# Block_HDMI_DP_DSI_USBSS_and_PCIe.net
KiCad netlist of a schematic drawn in Altium Designer
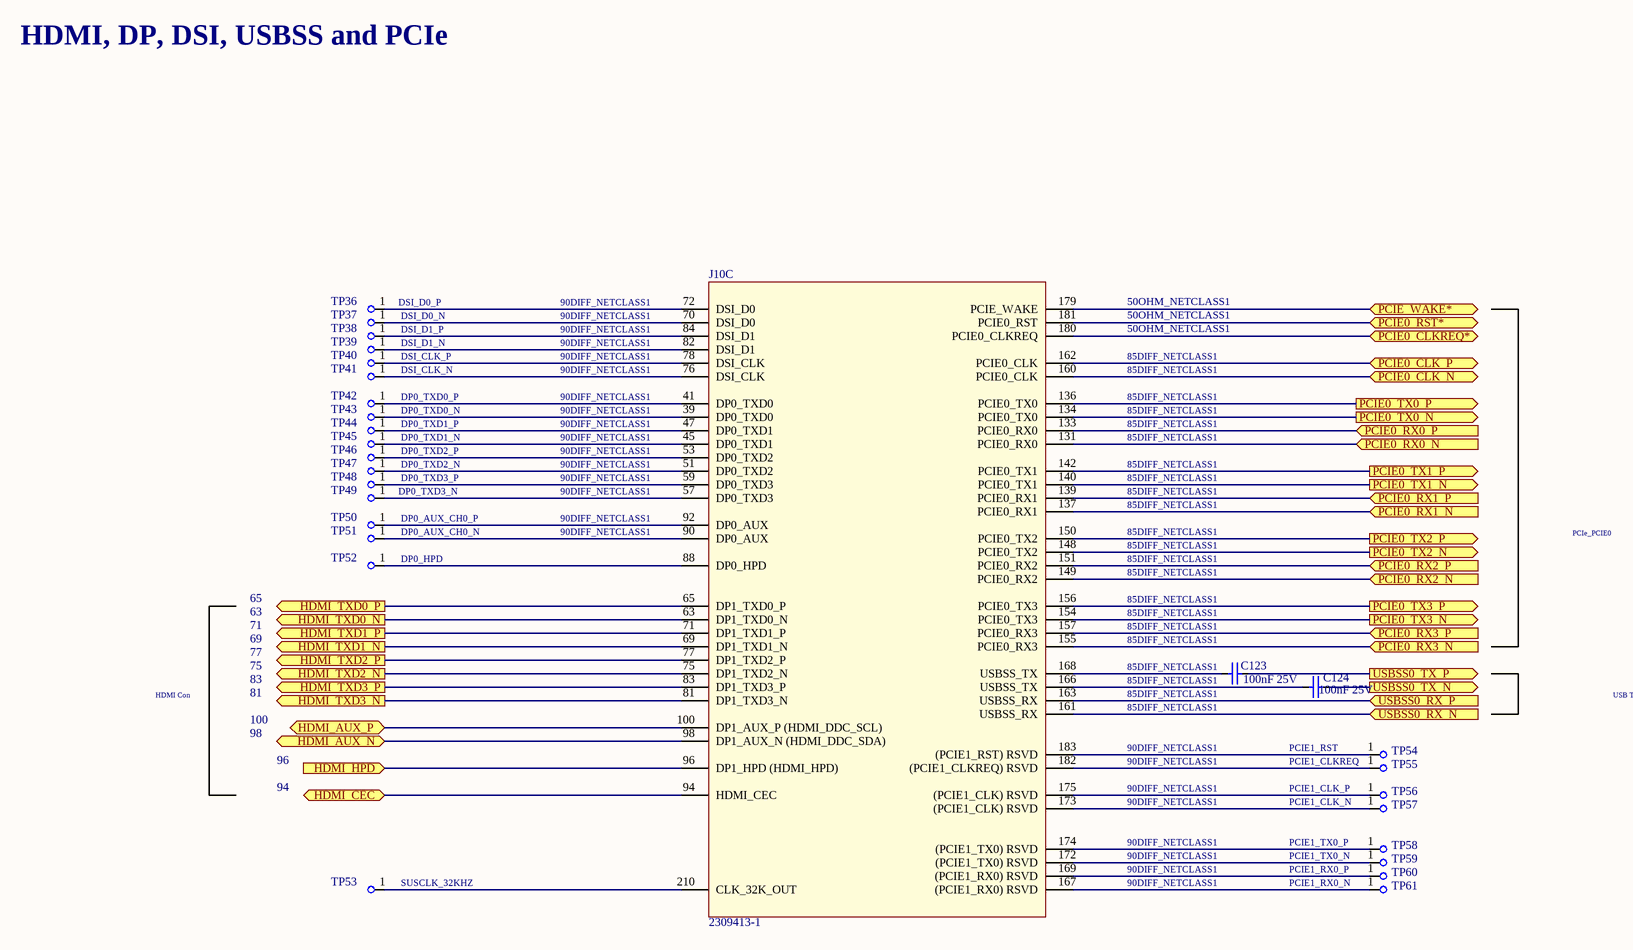
[diagram p0: Block_HDMI, DP, DSI, USBSS and PCIe.SchDoc]

(export (version "E")
  (design (tool "Eeschema 10.0.6"))
  (components
    (comp (ref "C123")
      (value "100nF 25V")
      (footprint "C0402")
      (description "CAP CER 0.1UF 25V X5R 0402 / High Value Multilayer Ceramic Capacitors (High dielectric type)")
      (fields
        (field (name "MANUFACTURER") "Taiyo Yuden")
        (field (name "MANUFACTURER PART NUMBER") "TMK105BJ104KV-F")
      )
      (libsource (lib "GM_Altium_Library") (part "TMK105BJ104KV-F"))
    )
    (comp (ref "C124")
      (value "100nF 25V")
      (footprint "C0402")
      (description "CAP CER 0.1UF 25V X5R 0402 / High Value Multilayer Ceramic Capacitors (High dielectric type)")
      (fields
        (field (name "MANUFACTURER") "Taiyo Yuden")
        (field (name "MANUFACTURER PART NUMBER") "TMK105BJ104KV-F")
      )
      (libsource (lib "GM_Altium_Library") (part "TMK105BJ104KV-F"))
    )
    (comp (ref "J10")
      (value "2309413-1")
      (footprint "2309413-1")
      (description "Conn DDR4 DIMM Socket SKT 260 POS 0.5mm Solder RA SMD T/R")
      (fields (field (name "MANUFACTURER") "TE Connectivity"))
      (libsource (lib "GM_Altium_Library") (part "2309413-1"))
    )
    (comp (ref "TP36")
      (value "DSI_D0_P")
      (footprint "TestPoint_Pad_D1.0mm")
      (libsource (lib "GM_Altium_Library") (part "TestPoint_D1mm"))
    )
    (comp (ref "TP37")
      (value "DSI_D0_N")
      (footprint "TestPoint_Pad_D1.0mm")
      (libsource (lib "GM_Altium_Library") (part "TestPoint_D1mm"))
    )
    (comp (ref "TP38")
      (value "DSI_D1_P")
      (footprint "TestPoint_Pad_D1.0mm")
      (libsource (lib "GM_Altium_Library") (part "TestPoint_D1mm"))
    )
    (comp (ref "TP39")
      (value "DSI_D1_N")
      (footprint "TestPoint_Pad_D1.0mm")
      (libsource (lib "GM_Altium_Library") (part "TestPoint_D1mm"))
    )
    (comp (ref "TP40")
      (value "DSI_CLK_P")
      (footprint "TestPoint_Pad_D1.0mm")
      (libsource (lib "GM_Altium_Library") (part "TestPoint_D1mm"))
    )
    (comp (ref "TP41")
      (value "DSI_CLK_N")
      (footprint "TestPoint_Pad_D1.0mm")
      (libsource (lib "GM_Altium_Library") (part "TestPoint_D1mm"))
    )
    (comp (ref "TP42")
      (value "DP0_TXD0_P")
      (footprint "TestPoint_Pad_D1.0mm")
      (libsource (lib "GM_Altium_Library") (part "TestPoint_D1mm"))
    )
    (comp (ref "TP43")
      (value "DP0_TXD0_N")
      (footprint "TestPoint_Pad_D1.0mm")
      (libsource (lib "GM_Altium_Library") (part "TestPoint_D1mm"))
    )
    (comp (ref "TP44")
      (value "DP0_TXD1_P")
      (footprint "TestPoint_Pad_D1.0mm")
      (libsource (lib "GM_Altium_Library") (part "TestPoint_D1mm"))
    )
    (comp (ref "TP45")
      (value "DP0_TXD1_N")
      (footprint "TestPoint_Pad_D1.0mm")
      (libsource (lib "GM_Altium_Library") (part "TestPoint_D1mm"))
    )
    (comp (ref "TP46")
      (value "DP0_TXD2_P")
      (footprint "TestPoint_Pad_D1.0mm")
      (libsource (lib "GM_Altium_Library") (part "TestPoint_D1mm"))
    )
    (comp (ref "TP47")
      (value "DP0_TXD2_N")
      (footprint "TestPoint_Pad_D1.0mm")
      (libsource (lib "GM_Altium_Library") (part "TestPoint_D1mm"))
    )
    (comp (ref "TP48")
      (value "DP0_TXD3_P")
      (footprint "TestPoint_Pad_D1.0mm")
      (libsource (lib "GM_Altium_Library") (part "TestPoint_D1mm"))
    )
    (comp (ref "TP49")
      (value "DP0_TXD3_N")
      (footprint "TestPoint_Pad_D1.0mm")
      (libsource (lib "GM_Altium_Library") (part "TestPoint_D1mm"))
    )
    (comp (ref "TP50")
      (value "DP0_AUX_CH0_P")
      (footprint "TestPoint_Pad_D1.0mm")
      (libsource (lib "GM_Altium_Library") (part "TestPoint_D1mm"))
    )
    (comp (ref "TP51")
      (value "DP0_AUX_CH0_N")
      (footprint "TestPoint_Pad_D1.0mm")
      (libsource (lib "GM_Altium_Library") (part "TestPoint_D1mm"))
    )
    (comp (ref "TP52")
      (value "DP0_HPD")
      (footprint "TestPoint_Pad_D1.0mm")
      (libsource (lib "GM_Altium_Library") (part "TestPoint_D1mm"))
    )
    (comp (ref "TP53")
      (value "SUSCLK_32KHZ")
      (footprint "TestPoint_Pad_D1.0mm")
      (libsource (lib "GM_Altium_Library") (part "TestPoint_D1mm"))
    )
    (comp (ref "TP54")
      (value "PCIE1_RST")
      (footprint "TestPoint_Pad_D1.0mm")
      (libsource (lib "GM_Altium_Library") (part "TestPoint_D1mm"))
    )
    (comp (ref "TP55")
      (value "PCIE1_CLKREQ")
      (footprint "TestPoint_Pad_D1.0mm")
      (libsource (lib "GM_Altium_Library") (part "TestPoint_D1mm"))
    )
    (comp (ref "TP56")
      (value "PCIE1_CLK_P")
      (footprint "TestPoint_Pad_D1.0mm")
      (libsource (lib "GM_Altium_Library") (part "TestPoint_D1mm"))
    )
    (comp (ref "TP57")
      (value "PCIE1_CLK_N")
      (footprint "TestPoint_Pad_D1.0mm")
      (libsource (lib "GM_Altium_Library") (part "TestPoint_D1mm"))
    )
    (comp (ref "TP58")
      (value "PCIE1_TX0_P")
      (footprint "TestPoint_Pad_D1.0mm")
      (libsource (lib "GM_Altium_Library") (part "TestPoint_D1mm"))
    )
    (comp (ref "TP59")
      (value "PCIE1_TX0_N")
      (footprint "TestPoint_Pad_D1.0mm")
      (libsource (lib "GM_Altium_Library") (part "TestPoint_D1mm"))
    )
    (comp (ref "TP60")
      (value "PCIE1_RX0_P")
      (footprint "TestPoint_Pad_D1.0mm")
      (libsource (lib "GM_Altium_Library") (part "TestPoint_D1mm"))
    )
    (comp (ref "TP61")
      (value "PCIE1_RX0_N")
      (footprint "TestPoint_Pad_D1.0mm")
      (libsource (lib "GM_Altium_Library") (part "TestPoint_D1mm"))
    )
  )
  (nets
    (net (code "1") (name "/HDMI_AUX_N") (class "Default")
      (node (ref "J10") (pin "98") (pinfunction "DP1_AUX_N_(HDMI_DDC_SDA)_98") (pintype "passive"))
    )
    (net (code "2") (name "/HDMI_AUX_P") (class "Default")
      (node (ref "J10") (pin "100") (pinfunction "DP1_AUX_P_(HDMI_DDC_SCL)_100") (pintype "passive"))
    )
    (net (code "3") (name "/HDMI_CEC") (class "Default")
      (node (ref "J10") (pin "94") (pinfunction "HDMI_CEC_94") (pintype "passive"))
    )
    (net (code "4") (name "/HDMI_HPD") (class "Default")
      (node (ref "J10") (pin "96") (pinfunction "DP1_HPD_(HDMI_HPD)_96") (pintype "passive"))
    )
    (net (code "5") (name "/HDMI_TXD0_N") (class "Default")
      (node (ref "J10") (pin "63") (pinfunction "DP1_TXD0_N_63") (pintype "passive"))
    )
    (net (code "6") (name "/HDMI_TXD0_P") (class "Default")
      (node (ref "J10") (pin "65") (pinfunction "DP1_TXD0_P_65") (pintype "passive"))
    )
    (net (code "7") (name "/HDMI_TXD1_N") (class "Default")
      (node (ref "J10") (pin "69") (pinfunction "DP1_TXD1_N_69") (pintype "passive"))
    )
    (net (code "8") (name "/HDMI_TXD1_P") (class "Default")
      (node (ref "J10") (pin "71") (pinfunction "DP1_TXD1_P_71") (pintype "passive"))
    )
    (net (code "9") (name "/HDMI_TXD2_N") (class "Default")
      (node (ref "J10") (pin "75") (pinfunction "DP1_TXD2_N_75") (pintype "passive"))
    )
    (net (code "10") (name "/HDMI_TXD2_P") (class "Default")
      (node (ref "J10") (pin "77") (pinfunction "DP1_TXD2_P_77") (pintype "passive"))
    )
    (net (code "11") (name "/HDMI_TXD3_N") (class "Default")
      (node (ref "J10") (pin "81") (pinfunction "DP1_TXD3_N_81") (pintype "passive"))
    )
    (net (code "12") (name "/HDMI_TXD3_P") (class "Default")
      (node (ref "J10") (pin "83") (pinfunction "DP1_TXD3_P_83") (pintype "passive"))
    )
    (net (code "13") (name "/PCIE0_CLKREQ*") (class "Default")
      (node (ref "J10") (pin "180") (pinfunction "PCIE0_CLKREQ_180") (pintype "passive"))
    )
    (net (code "14") (name "/PCIE0_CLK_N") (class "Default")
      (node (ref "J10") (pin "160") (pinfunction "PCIE0_CLK_160") (pintype "passive"))
    )
    (net (code "15") (name "/PCIE0_CLK_P") (class "Default")
      (node (ref "J10") (pin "162") (pinfunction "PCIE0_CLK_162") (pintype "passive"))
    )
    (net (code "16") (name "/PCIE0_RST*") (class "Default")
      (node (ref "J10") (pin "181") (pinfunction "PCIE0_RST_181") (pintype "passive"))
    )
    (net (code "17") (name "/PCIE0_RX0_N") (class "Default")
      (node (ref "J10") (pin "131") (pinfunction "PCIE0_RX0_131") (pintype "passive"))
    )
    (net (code "18") (name "/PCIE0_RX0_P") (class "Default")
      (node (ref "J10") (pin "133") (pinfunction "PCIE0_RX0_133") (pintype "passive"))
    )
    (net (code "19") (name "/PCIE0_RX1_N") (class "Default")
      (node (ref "J10") (pin "137") (pinfunction "PCIE0_RX1_137") (pintype "passive"))
    )
    (net (code "20") (name "/PCIE0_RX1_P") (class "Default")
      (node (ref "J10") (pin "139") (pinfunction "PCIE0_RX1_139") (pintype "passive"))
    )
    (net (code "21") (name "/PCIE0_RX2_N") (class "Default")
      (node (ref "J10") (pin "149") (pinfunction "PCIE0_RX2_149") (pintype "passive"))
    )
    (net (code "22") (name "/PCIE0_RX2_P") (class "Default")
      (node (ref "J10") (pin "151") (pinfunction "PCIE0_RX2_151") (pintype "passive"))
    )
    (net (code "23") (name "/PCIE0_RX3_N") (class "Default")
      (node (ref "J10") (pin "155") (pinfunction "PCIE0_RX3_155") (pintype "passive"))
    )
    (net (code "24") (name "/PCIE0_RX3_P") (class "Default")
      (node (ref "J10") (pin "157") (pinfunction "PCIE0_RX3_157") (pintype "passive"))
    )
    (net (code "25") (name "/PCIE0_TX0_N") (class "Default")
      (node (ref "J10") (pin "134") (pinfunction "PCIE0_TX0_134") (pintype "passive"))
    )
    (net (code "26") (name "/PCIE0_TX0_P") (class "Default")
      (node (ref "J10") (pin "136") (pinfunction "PCIE0_TX0_136") (pintype "passive"))
    )
    (net (code "27") (name "/PCIE0_TX1_N") (class "Default")
      (node (ref "J10") (pin "140") (pinfunction "PCIE0_TX1_140") (pintype "passive"))
    )
    (net (code "28") (name "/PCIE0_TX1_P") (class "Default")
      (node (ref "J10") (pin "142") (pinfunction "PCIE0_TX1_142") (pintype "passive"))
    )
    (net (code "29") (name "/PCIE0_TX2_N") (class "Default")
      (node (ref "J10") (pin "148") (pinfunction "PCIE0_TX2_148") (pintype "passive"))
    )
    (net (code "30") (name "/PCIE0_TX2_P") (class "Default")
      (node (ref "J10") (pin "150") (pinfunction "PCIE0_TX2_150") (pintype "passive"))
    )
    (net (code "31") (name "/PCIE0_TX3_N") (class "Default")
      (node (ref "J10") (pin "154") (pinfunction "PCIE0_TX3_154") (pintype "passive"))
    )
    (net (code "32") (name "/PCIE0_TX3_P") (class "Default")
      (node (ref "J10") (pin "156") (pinfunction "PCIE0_TX3_156") (pintype "passive"))
    )
    (net (code "33") (name "/PCIE_WAKE*") (class "Default")
      (node (ref "J10") (pin "179") (pinfunction "PCIE_WAKE_179") (pintype "passive"))
    )
    (net (code "34") (name "/USBSS0_RX_N") (class "Default")
      (node (ref "J10") (pin "161") (pinfunction "USBSS_RX_161") (pintype "passive"))
    )
    (net (code "35") (name "/USBSS0_RX_P") (class "Default")
      (node (ref "J10") (pin "163") (pinfunction "USBSS_RX_163") (pintype "passive"))
    )
    (net (code "36") (name "/USBSS0_TX_N") (class "Default")
      (node (ref "C124") (pin "2") (pinfunction "2_2") (pintype "passive"))
    )
    (net (code "37") (name "/USBSS0_TX_P") (class "Default")
      (node (ref "C123") (pin "2") (pinfunction "2_2") (pintype "passive"))
    )
    (net (code "38") (name "Net-(C123-Pad1)") (class "Default")
      (node (ref "C123") (pin "1") (pinfunction "1_1") (pintype "passive"))
      (node (ref "J10") (pin "168") (pinfunction "USBSS_TX_168") (pintype "passive"))
    )
    (net (code "39") (name "Net-(C124-Pad1)") (class "Default")
      (node (ref "C124") (pin "1") (pinfunction "1_1") (pintype "passive"))
      (node (ref "J10") (pin "166") (pinfunction "USBSS_TX_166") (pintype "passive"))
    )
    (net (code "40") (name "Net-(J10C-(PCIE1_CLK)_RSVD-Pad173)") (class "Default")
      (node (ref "J10") (pin "173") (pinfunction "(PCIE1_CLK)_RSVD_173") (pintype "passive"))
      (node (ref "TP57") (pin "1") (pinfunction "1_1") (pintype "passive"))
    )
    (net (code "41") (name "Net-(J10C-(PCIE1_CLK)_RSVD-Pad175)") (class "Default")
      (node (ref "J10") (pin "175") (pinfunction "(PCIE1_CLK)_RSVD_175") (pintype "passive"))
      (node (ref "TP56") (pin "1") (pinfunction "1_1") (pintype "passive"))
    )
    (net (code "42") (name "Net-(J10C-(PCIE1_CLKREQ)_RSVD)") (class "Default")
      (node (ref "J10") (pin "182") (pinfunction "(PCIE1_CLKREQ)_RSVD_182") (pintype "passive"))
      (node (ref "TP55") (pin "1") (pinfunction "1_1") (pintype "passive"))
    )
    (net (code "43") (name "Net-(J10C-(PCIE1_RST)_RSVD)") (class "Default")
      (node (ref "J10") (pin "183") (pinfunction "(PCIE1_RST)_RSVD_183") (pintype "passive"))
      (node (ref "TP54") (pin "1") (pinfunction "1_1") (pintype "passive"))
    )
    (net (code "44") (name "Net-(J10C-(PCIE1_RX0)_RSVD-Pad167)") (class "Default")
      (node (ref "J10") (pin "167") (pinfunction "(PCIE1_RX0)_RSVD_167") (pintype "passive"))
      (node (ref "TP61") (pin "1") (pinfunction "1_1") (pintype "passive"))
    )
    (net (code "45") (name "Net-(J10C-(PCIE1_RX0)_RSVD-Pad169)") (class "Default")
      (node (ref "J10") (pin "169") (pinfunction "(PCIE1_RX0)_RSVD_169") (pintype "passive"))
      (node (ref "TP60") (pin "1") (pinfunction "1_1") (pintype "passive"))
    )
    (net (code "46") (name "Net-(J10C-(PCIE1_TX0)_RSVD-Pad172)") (class "Default")
      (node (ref "J10") (pin "172") (pinfunction "(PCIE1_TX0)_RSVD_172") (pintype "passive"))
      (node (ref "TP59") (pin "1") (pinfunction "1_1") (pintype "passive"))
    )
    (net (code "47") (name "Net-(J10C-(PCIE1_TX0)_RSVD-Pad174)") (class "Default")
      (node (ref "J10") (pin "174") (pinfunction "(PCIE1_TX0)_RSVD_174") (pintype "passive"))
      (node (ref "TP58") (pin "1") (pinfunction "1_1") (pintype "passive"))
    )
    (net (code "48") (name "Net-(J10C-CLK_32K_OUT)") (class "Default")
      (node (ref "J10") (pin "210") (pinfunction "CLK_32K_OUT_210") (pintype "passive"))
      (node (ref "TP53") (pin "1") (pinfunction "1_1") (pintype "passive"))
    )
    (net (code "49") (name "Net-(J10C-DP0_AUX-Pad90)") (class "Default")
      (node (ref "J10") (pin "90") (pinfunction "DP0_AUX_90") (pintype "passive"))
      (node (ref "TP51") (pin "1") (pinfunction "1_1") (pintype "passive"))
    )
    (net (code "50") (name "Net-(J10C-DP0_AUX-Pad92)") (class "Default")
      (node (ref "J10") (pin "92") (pinfunction "DP0_AUX_92") (pintype "passive"))
      (node (ref "TP50") (pin "1") (pinfunction "1_1") (pintype "passive"))
    )
    (net (code "51") (name "Net-(J10C-DP0_HPD)") (class "Default")
      (node (ref "J10") (pin "88") (pinfunction "DP0_HPD_88") (pintype "passive"))
      (node (ref "TP52") (pin "1") (pinfunction "1_1") (pintype "passive"))
    )
    (net (code "52") (name "Net-(J10C-DP0_TXD0-Pad39)") (class "Default")
      (node (ref "J10") (pin "39") (pinfunction "DP0_TXD0_39") (pintype "passive"))
      (node (ref "TP43") (pin "1") (pinfunction "1_1") (pintype "passive"))
    )
    (net (code "53") (name "Net-(J10C-DP0_TXD0-Pad41)") (class "Default")
      (node (ref "J10") (pin "41") (pinfunction "DP0_TXD0_41") (pintype "passive"))
      (node (ref "TP42") (pin "1") (pinfunction "1_1") (pintype "passive"))
    )
    (net (code "54") (name "Net-(J10C-DP0_TXD1-Pad45)") (class "Default")
      (node (ref "J10") (pin "45") (pinfunction "DP0_TXD1_45") (pintype "passive"))
      (node (ref "TP45") (pin "1") (pinfunction "1_1") (pintype "passive"))
    )
    (net (code "55") (name "Net-(J10C-DP0_TXD1-Pad47)") (class "Default")
      (node (ref "J10") (pin "47") (pinfunction "DP0_TXD1_47") (pintype "passive"))
      (node (ref "TP44") (pin "1") (pinfunction "1_1") (pintype "passive"))
    )
    (net (code "56") (name "Net-(J10C-DP0_TXD2-Pad51)") (class "Default")
      (node (ref "J10") (pin "51") (pinfunction "DP0_TXD2_51") (pintype "passive"))
      (node (ref "TP47") (pin "1") (pinfunction "1_1") (pintype "passive"))
    )
    (net (code "57") (name "Net-(J10C-DP0_TXD2-Pad53)") (class "Default")
      (node (ref "J10") (pin "53") (pinfunction "DP0_TXD2_53") (pintype "passive"))
      (node (ref "TP46") (pin "1") (pinfunction "1_1") (pintype "passive"))
    )
    (net (code "58") (name "Net-(J10C-DP0_TXD3-Pad57)") (class "Default")
      (node (ref "J10") (pin "57") (pinfunction "DP0_TXD3_57") (pintype "passive"))
      (node (ref "TP49") (pin "1") (pinfunction "1_1") (pintype "passive"))
    )
    (net (code "59") (name "Net-(J10C-DP0_TXD3-Pad59)") (class "Default")
      (node (ref "J10") (pin "59") (pinfunction "DP0_TXD3_59") (pintype "passive"))
      (node (ref "TP48") (pin "1") (pinfunction "1_1") (pintype "passive"))
    )
    (net (code "60") (name "Net-(J10C-DSI_CLK-Pad76)") (class "Default")
      (node (ref "J10") (pin "76") (pinfunction "DSI_CLK_76") (pintype "passive"))
      (node (ref "TP41") (pin "1") (pinfunction "1_1") (pintype "passive"))
    )
    (net (code "61") (name "Net-(J10C-DSI_CLK-Pad78)") (class "Default")
      (node (ref "J10") (pin "78") (pinfunction "DSI_CLK_78") (pintype "passive"))
      (node (ref "TP40") (pin "1") (pinfunction "1_1") (pintype "passive"))
    )
    (net (code "62") (name "Net-(J10C-DSI_D0-Pad70)") (class "Default")
      (node (ref "J10") (pin "70") (pinfunction "DSI_D0_70") (pintype "passive"))
      (node (ref "TP37") (pin "1") (pinfunction "1_1") (pintype "passive"))
    )
    (net (code "63") (name "Net-(J10C-DSI_D0-Pad72)") (class "Default")
      (node (ref "J10") (pin "72") (pinfunction "DSI_D0_72") (pintype "passive"))
      (node (ref "TP36") (pin "1") (pinfunction "1_1") (pintype "passive"))
    )
    (net (code "64") (name "Net-(J10C-DSI_D1-Pad82)") (class "Default")
      (node (ref "J10") (pin "82") (pinfunction "DSI_D1_82") (pintype "passive"))
      (node (ref "TP39") (pin "1") (pinfunction "1_1") (pintype "passive"))
    )
    (net (code "65") (name "Net-(J10C-DSI_D1-Pad84)") (class "Default")
      (node (ref "J10") (pin "84") (pinfunction "DSI_D1_84") (pintype "passive"))
      (node (ref "TP38") (pin "1") (pinfunction "1_1") (pintype "passive"))
    )
  )
)
